# plen_headboard.net
KiCad netlist of a schematic drawn in EAGLE
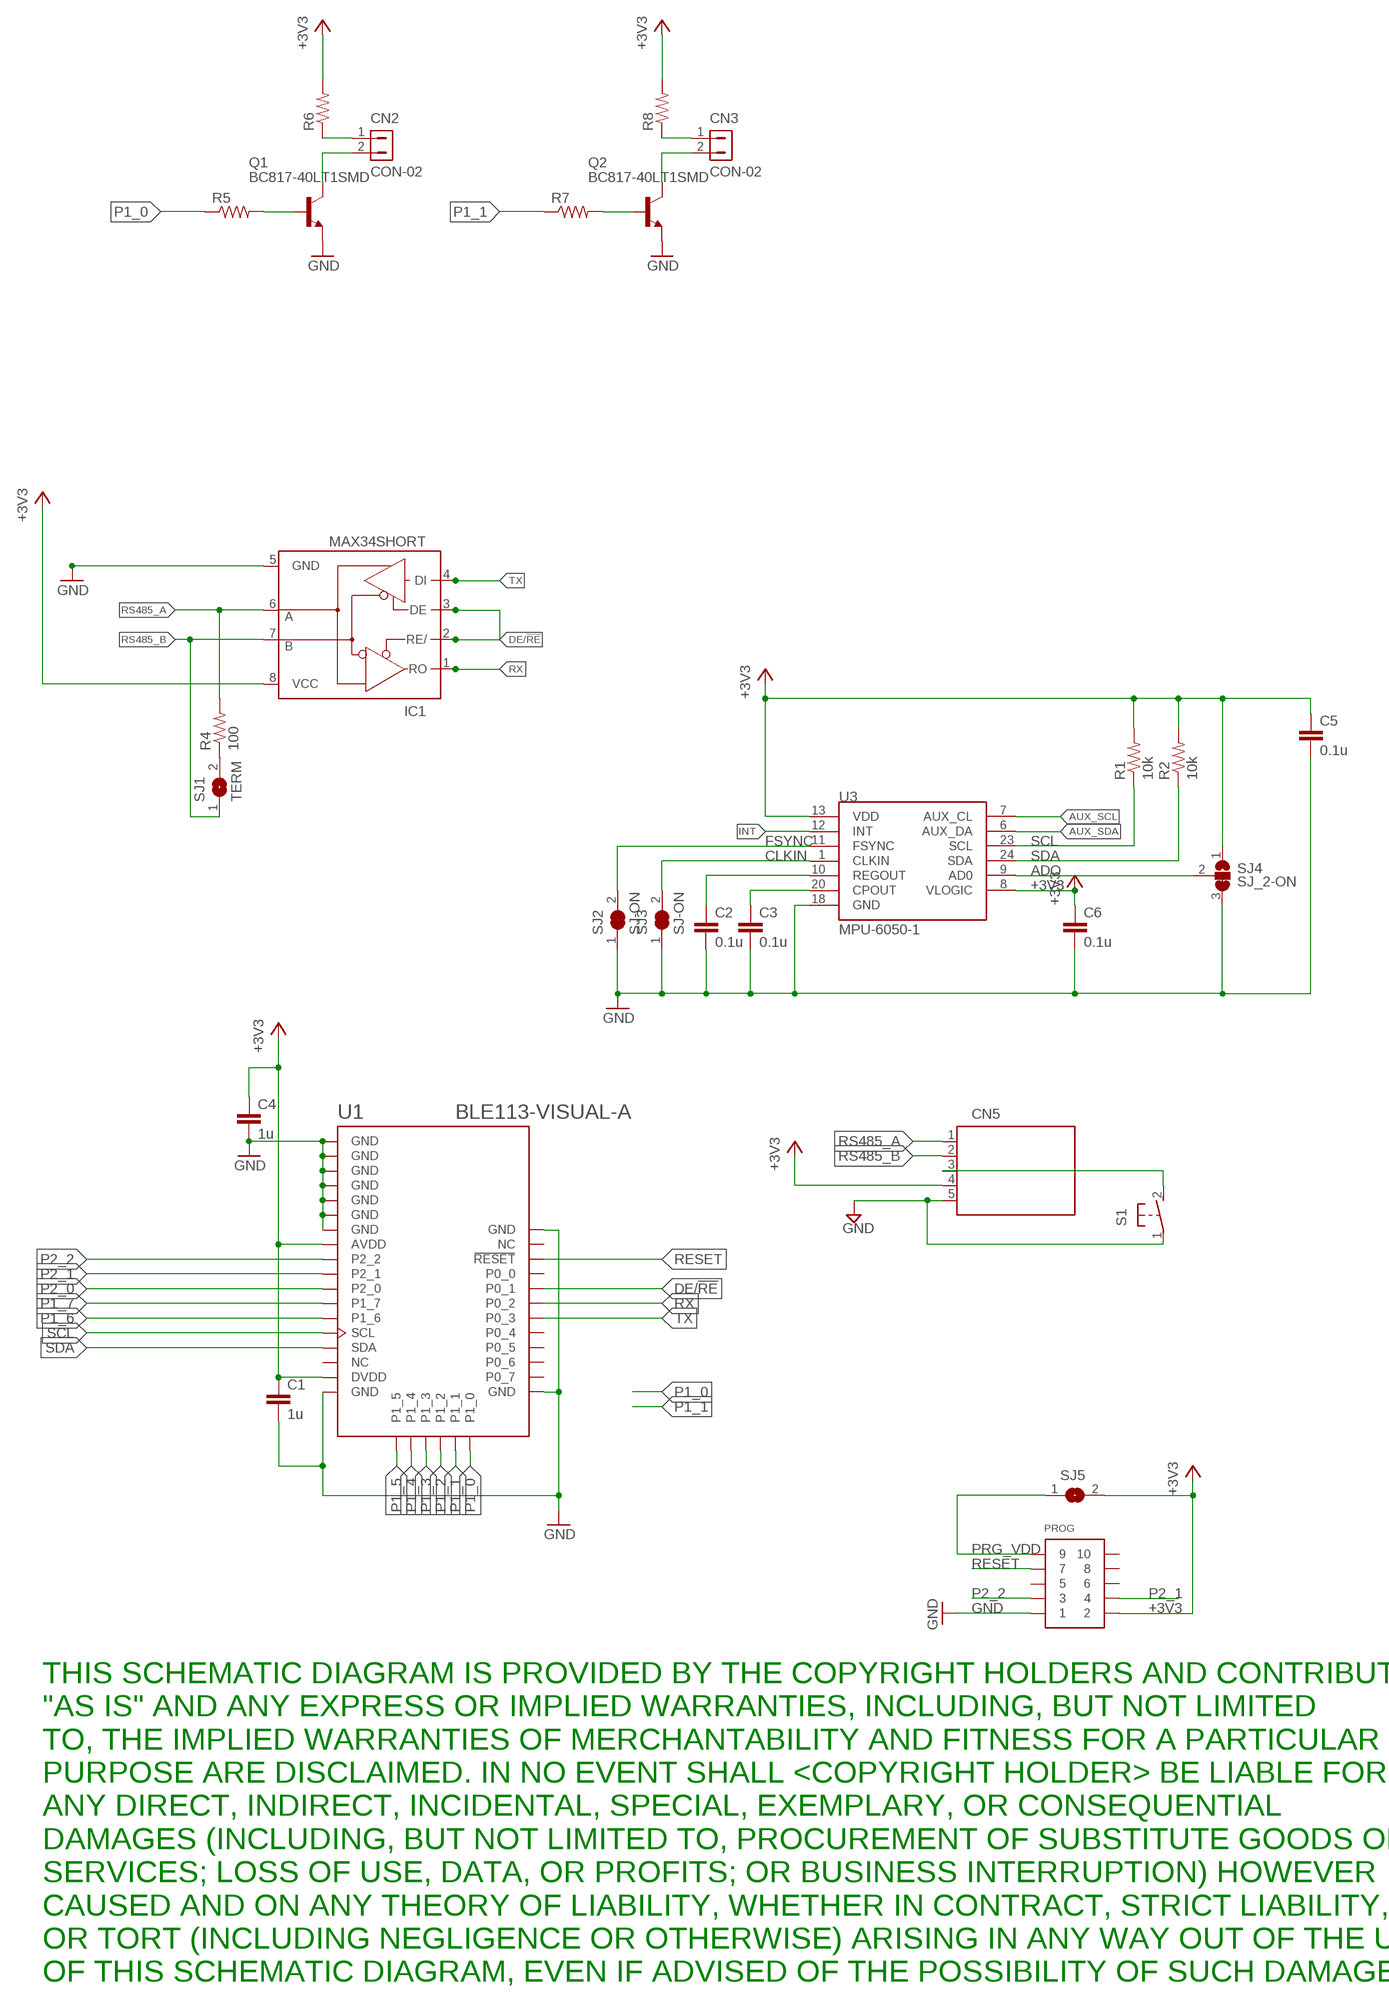
[diagram p0: schematic, sheet 1]

(export (version "E")
  (design (tool "Eeschema 10.0.6"))
  (components
    (comp (ref "C1")
      (value "1u")
      (footprint "eagle-import:C0603")
      (libsource (lib "eagle-import") (part "C-EUC0603"))
    )
    (comp (ref "C2")
      (value "0.1u")
      (footprint "eagle-import:C0603")
      (libsource (lib "eagle-import") (part "C-EUC0603"))
    )
    (comp (ref "C3")
      (value "0.1u")
      (footprint "eagle-import:C0603")
      (libsource (lib "eagle-import") (part "C-EUC0603"))
    )
    (comp (ref "C4")
      (value "1u")
      (footprint "eagle-import:C0603")
      (libsource (lib "eagle-import") (part "C-EUC0603"))
    )
    (comp (ref "C5")
      (value "0.1u")
      (footprint "eagle-import:C0603")
      (libsource (lib "eagle-import") (part "C-EUC0603"))
    )
    (comp (ref "C6")
      (value "0.1u")
      (footprint "eagle-import:C0603")
      (libsource (lib "eagle-import") (part "C-EUC0603"))
    )
    (comp (ref "CN2")
      (value "CON-02")
      (footprint "eagle-import:SIP-100-02")
      (libsource (lib "eagle-import") (part "CON-02"))
    )
    (comp (ref "CN3")
      (value "CON-02")
      (footprint "eagle-import:SIP-100-02")
      (libsource (lib "eagle-import") (part "CON-02"))
    )
    (comp (ref "CN5")
      (value "5PINZH")
      (footprint "eagle-import:ZH-5")
      (libsource (lib "eagle-import") (part "5PINZH"))
    )
    (comp (ref "IC1")
      (value "MAX34SHORT")
      (footprint "eagle-import:SO08SHORT")
      (libsource (lib "eagle-import") (part "MAX34SHORT"))
    )
    (comp (ref "PROG")
      (value "CONN_5-2-FTSH-V")
      (footprint "eagle-import:FTSH-105-DV")
      (libsource (lib "eagle-import") (part "CONN_5-2-FTSH-V"))
    )
    (comp (ref "Q1")
      (value "BC817-40LT1SMD")
      (footprint "eagle-import:SOT23-BEC")
      (libsource (lib "eagle-import") (part "BC817SMD-40LT1"))
    )
    (comp (ref "Q2")
      (value "BC817-40LT1SMD")
      (footprint "eagle-import:SOT23-BEC")
      (libsource (lib "eagle-import") (part "BC817SMD-40LT1"))
    )
    (comp (ref "R1")
      (value "10k")
      (footprint "eagle-import:R0603")
      (libsource (lib "eagle-import") (part "R-US_R0603"))
    )
    (comp (ref "R2")
      (value "10k")
      (footprint "eagle-import:R0603")
      (libsource (lib "eagle-import") (part "R-US_R0603"))
    )
    (comp (ref "R4")
      (value "100")
      (footprint "eagle-import:R0603")
      (libsource (lib "eagle-import") (part "R-US_R0603"))
    )
    (comp (ref "R5")
      (value "R-US_R0603")
      (footprint "eagle-import:R0603")
      (libsource (lib "eagle-import") (part "R-US_R0603"))
    )
    (comp (ref "R6")
      (value "R-US_R0603")
      (footprint "eagle-import:R0603")
      (libsource (lib "eagle-import") (part "R-US_R0603"))
    )
    (comp (ref "R7")
      (value "R-US_R0603")
      (footprint "eagle-import:R0603")
      (libsource (lib "eagle-import") (part "R-US_R0603"))
    )
    (comp (ref "R8")
      (value "R-US_R0603")
      (footprint "eagle-import:R0603")
      (libsource (lib "eagle-import") (part "R-US_R0603"))
    )
    (comp (ref "S1")
      (value "31-XX")
      (footprint "eagle-import:B3F-31XX")
      (fields (field (name "MPN") "B3F-3100"))
      (libsource (lib "eagle-import") (part "31-XX"))
    )
    (comp (ref "SJ1")
      (value "TERM")
      (footprint "eagle-import:SJ")
      (libsource (lib "eagle-import") (part "SJ"))
    )
    (comp (ref "SJ2")
      (value "SJ-ON")
      (footprint "eagle-import:SJ-ON")
      (libsource (lib "eagle-import") (part "SJ-ON"))
    )
    (comp (ref "SJ3")
      (value "SJ-ON")
      (footprint "eagle-import:SJ-ON")
      (libsource (lib "eagle-import") (part "SJ-ON"))
    )
    (comp (ref "SJ4")
      (value "SJ_2-ON")
      (footprint "eagle-import:SJ_2-ON")
      (libsource (lib "eagle-import") (part "SJ_2-ON"))
    )
    (comp (ref "SJ5") (value "SJ") (footprint "eagle-import:SJ") (libsource (lib "eagle-import") (part "SJ")))
    (comp (ref "U1")
      (value "BLE113-VISUAL-A")
      (footprint "eagle-import:BLE113-A")
      (libsource (lib "eagle-import") (part "BLE113-VISUAL-A"))
    )
    (comp (ref "U3")
      (value "MPU-6050-1")
      (footprint "eagle-import:QFN-24-4MM2")
      (libsource (lib "eagle-import") (part "MPU-6050-1"))
    )
  )
  (nets
    (net (code "1") (name "+3V3") (class "Default")
      (node (ref "C1") (pin "1") (pinfunction "1_1") (pintype "passive"))
      (node (ref "C4") (pin "1") (pinfunction "1_1") (pintype "passive"))
      (node (ref "C5") (pin "1") (pinfunction "1_1") (pintype "passive"))
      (node (ref "C6") (pin "1") (pinfunction "1_1") (pintype "passive"))
      (node (ref "CN5") (pin "4") (pinfunction "4_4") (pintype "passive"))
      (node (ref "IC1") (pin "8") (pinfunction "VCC_8") (pintype "power_in"))
      (node (ref "PROG") (pin "2") (pinfunction "2_2") (pintype "bidirectional"))
      (node (ref "R1") (pin "2") (pinfunction "2_2") (pintype "passive"))
      (node (ref "R2") (pin "2") (pinfunction "2_2") (pintype "passive"))
      (node (ref "R6") (pin "2") (pinfunction "2_2") (pintype "passive"))
      (node (ref "R8") (pin "2") (pinfunction "2_2") (pintype "passive"))
      (node (ref "SJ4") (pin "1") (pinfunction "1_1") (pintype "passive"))
      (node (ref "SJ5") (pin "2") (pinfunction "2_2") (pintype "passive"))
      (node (ref "U1") (pin "AVDD") (pinfunction "AVDD_AVDD") (pintype "power_in"))
      (node (ref "U1") (pin "DVDD") (pinfunction "DVDD_DVDD") (pintype "power_in"))
      (node (ref "U3") (pin "13") (pinfunction "VDD_13") (pintype "bidirectional"))
      (node (ref "U3") (pin "8") (pinfunction "VLOGIC_8") (pintype "bidirectional"))
    )
    (net (code "2") (name "/ADO") (class "Default")
      (node (ref "SJ4") (pin "2") (pinfunction "2_2") (pintype "passive"))
      (node (ref "U3") (pin "9") (pinfunction "AD0_9") (pintype "bidirectional"))
    )
    (net (code "3") (name "/CLKIN") (class "Default")
      (node (ref "SJ3") (pin "2") (pinfunction "2_2") (pintype "passive"))
      (node (ref "U3") (pin "1") (pinfunction "CLKIN_1") (pintype "bidirectional"))
    )
    (net (code "4") (name "/DE{slash}~{RE}") (class "Default")
      (node (ref "IC1") (pin "2") (pinfunction "RE/_2") (pintype "input"))
      (node (ref "IC1") (pin "3") (pinfunction "DE_3") (pintype "input"))
      (node (ref "U1") (pin "P0_1") (pinfunction "P0_1_P0_1") (pintype "bidirectional"))
    )
    (net (code "5") (name "/FSYNC") (class "Default")
      (node (ref "SJ2") (pin "2") (pinfunction "2_2") (pintype "passive"))
      (node (ref "U3") (pin "11") (pinfunction "FSYNC_11") (pintype "bidirectional"))
    )
    (net (code "6") (name "/PRG_VDD") (class "Default")
      (node (ref "PROG") (pin "9") (pinfunction "9_9") (pintype "bidirectional"))
      (node (ref "SJ5") (pin "1") (pinfunction "1_1") (pintype "passive"))
    )
    (net (code "7") (name "AUX_SCL") (class "Default")
      (node (ref "U3") (pin "7") (pinfunction "AUX_CL_7") (pintype "bidirectional"))
    )
    (net (code "8") (name "AUX_SDA") (class "Default")
      (node (ref "U3") (pin "6") (pinfunction "AUX_DA_6") (pintype "bidirectional"))
    )
    (net (code "9") (name "GND") (class "Default")
      (node (ref "C1") (pin "2") (pinfunction "2_2") (pintype "passive"))
      (node (ref "C2") (pin "2") (pinfunction "2_2") (pintype "passive"))
      (node (ref "C3") (pin "2") (pinfunction "2_2") (pintype "passive"))
      (node (ref "C4") (pin "2") (pinfunction "2_2") (pintype "passive"))
      (node (ref "C5") (pin "2") (pinfunction "2_2") (pintype "passive"))
      (node (ref "C6") (pin "2") (pinfunction "2_2") (pintype "passive"))
      (node (ref "CN5") (pin "5") (pinfunction "5_5") (pintype "passive"))
      (node (ref "IC1") (pin "5") (pinfunction "GND_5") (pintype "power_in"))
      (node (ref "PROG") (pin "1") (pinfunction "1_1") (pintype "bidirectional"))
      (node (ref "Q1") (pin "E") (pinfunction "E_E") (pintype "passive"))
      (node (ref "Q2") (pin "E") (pinfunction "E_E") (pintype "passive"))
      (node (ref "S1") (pin "1") (pinfunction "P_1") (pintype "passive"))
      (node (ref "SJ2") (pin "1") (pinfunction "1_1") (pintype "passive"))
      (node (ref "SJ3") (pin "1") (pinfunction "1_1") (pintype "passive"))
      (node (ref "SJ4") (pin "3") (pinfunction "3_3") (pintype "passive"))
      (node (ref "U1") (pin "GND") (pinfunction "GND_GND") (pintype "power_in"))
      (node (ref "U1") (pin "GND@10") (pinfunction "GND_GND@10") (pintype "power_in"))
      (node (ref "U1") (pin "GND@2") (pinfunction "GND_GND@2") (pintype "power_in"))
      (node (ref "U1") (pin "GND@3") (pinfunction "GND_GND@3") (pintype "power_in"))
      (node (ref "U1") (pin "GND@4") (pinfunction "GND_GND@4") (pintype "power_in"))
      (node (ref "U1") (pin "GND@5") (pinfunction "GND_GND@5") (pintype "power_in"))
      (node (ref "U1") (pin "GND@6") (pinfunction "GND_GND@6") (pintype "power_in"))
      (node (ref "U1") (pin "GND@7") (pinfunction "GND_GND@7") (pintype "power_in"))
      (node (ref "U1") (pin "GND@8") (pinfunction "GND_GND@8") (pintype "power_in"))
      (node (ref "U1") (pin "GND@9") (pinfunction "GND_GND@9") (pintype "power_in"))
      (node (ref "U3") (pin "18") (pinfunction "GND_18") (pintype "bidirectional"))
    )
    (net (code "10") (name "INT") (class "Default")
      (node (ref "U3") (pin "12") (pinfunction "INT_12") (pintype "bidirectional"))
    )
    (net (code "11") (name "Net-(CN2-Pad1)") (class "Default")
      (node (ref "CN2") (pin "1") (pinfunction "1_1") (pintype "passive"))
      (node (ref "R6") (pin "1") (pinfunction "1_1") (pintype "passive"))
    )
    (net (code "12") (name "Net-(CN2-Pad2)") (class "Default")
      (node (ref "CN2") (pin "2") (pinfunction "2_2") (pintype "passive"))
      (node (ref "Q1") (pin "C") (pinfunction "C_C") (pintype "passive"))
    )
    (net (code "13") (name "Net-(CN3-Pad1)") (class "Default")
      (node (ref "CN3") (pin "1") (pinfunction "1_1") (pintype "passive"))
      (node (ref "R8") (pin "1") (pinfunction "1_1") (pintype "passive"))
    )
    (net (code "14") (name "Net-(CN3-Pad2)") (class "Default")
      (node (ref "CN3") (pin "2") (pinfunction "2_2") (pintype "passive"))
      (node (ref "Q2") (pin "C") (pinfunction "C_C") (pintype "passive"))
    )
    (net (code "15") (name "Net-(Q1-PadB)") (class "Default")
      (node (ref "Q1") (pin "B") (pinfunction "B_B") (pintype "passive"))
      (node (ref "R5") (pin "2") (pinfunction "2_2") (pintype "passive"))
    )
    (net (code "16") (name "Net-(Q2-PadB)") (class "Default")
      (node (ref "Q2") (pin "B") (pinfunction "B_B") (pintype "passive"))
      (node (ref "R7") (pin "2") (pinfunction "2_2") (pintype "passive"))
    )
    (net (code "17") (name "Net-(R4-Pad1)") (class "Default")
      (node (ref "R4") (pin "1") (pinfunction "1_1") (pintype "passive"))
      (node (ref "SJ1") (pin "2") (pinfunction "2_2") (pintype "passive"))
    )
    (net (code "18") (name "Net-(S1-S)") (class "Default")
      (node (ref "CN5") (pin "3") (pinfunction "3_3") (pintype "passive"))
      (node (ref "S1") (pin "2") (pinfunction "S_2") (pintype "passive"))
    )
    (net (code "19") (name "Net-(U3-CPOUT)") (class "Default")
      (node (ref "C3") (pin "1") (pinfunction "1_1") (pintype "passive"))
      (node (ref "U3") (pin "20") (pinfunction "CPOUT_20") (pintype "bidirectional"))
    )
    (net (code "20") (name "Net-(U3-REGOUT)") (class "Default")
      (node (ref "C2") (pin "1") (pinfunction "1_1") (pintype "passive"))
      (node (ref "U3") (pin "10") (pinfunction "REGOUT_10") (pintype "bidirectional"))
    )
    (net (code "21") (name "P1_0") (class "Default")
      (node (ref "R5") (pin "1") (pinfunction "1_1") (pintype "passive"))
      (node (ref "U1") (pin "P1_0") (pinfunction "P1_0_P1_0") (pintype "bidirectional"))
    )
    (net (code "22") (name "P1_1") (class "Default")
      (node (ref "R7") (pin "1") (pinfunction "1_1") (pintype "passive"))
      (node (ref "U1") (pin "P1_1") (pinfunction "P1_1_P1_1") (pintype "bidirectional"))
    )
    (net (code "23") (name "P1_2") (class "Default")
      (node (ref "U1") (pin "P1_2") (pinfunction "P1_2_P1_2") (pintype "bidirectional"))
    )
    (net (code "24") (name "P1_3") (class "Default")
      (node (ref "U1") (pin "P1_3") (pinfunction "P1_3_P1_3") (pintype "bidirectional"))
    )
    (net (code "25") (name "P1_4") (class "Default")
      (node (ref "U1") (pin "P1_4") (pinfunction "P1_4_P1_4") (pintype "bidirectional"))
    )
    (net (code "26") (name "P1_5") (class "Default")
      (node (ref "U1") (pin "P1_5") (pinfunction "P1_5_P1_5") (pintype "bidirectional"))
    )
    (net (code "27") (name "P1_6") (class "Default")
      (node (ref "U1") (pin "P1_6") (pinfunction "P1_6_P1_6") (pintype "bidirectional"))
    )
    (net (code "28") (name "P1_7") (class "Default")
      (node (ref "U1") (pin "P1_7") (pinfunction "P1_7_P1_7") (pintype "bidirectional"))
    )
    (net (code "29") (name "P2_0") (class "Default")
      (node (ref "U1") (pin "P2_0") (pinfunction "P2_0_P2_0") (pintype "bidirectional"))
    )
    (net (code "30") (name "P2_1") (class "Default")
      (node (ref "PROG") (pin "4") (pinfunction "4_4") (pintype "bidirectional"))
      (node (ref "U1") (pin "P2_1") (pinfunction "P2_1_P2_1") (pintype "bidirectional"))
    )
    (net (code "31") (name "P2_2") (class "Default")
      (node (ref "PROG") (pin "3") (pinfunction "3_3") (pintype "bidirectional"))
      (node (ref "U1") (pin "P2_2") (pinfunction "P2_2_P2_2") (pintype "bidirectional"))
    )
    (net (code "32") (name "RESET") (class "Default")
      (node (ref "PROG") (pin "7") (pinfunction "7_7") (pintype "bidirectional"))
      (node (ref "U1") (pin "RESET") (pinfunction "RESET_RESET") (pintype "input"))
    )
    (net (code "33") (name "RS485_A") (class "Default")
      (node (ref "CN5") (pin "1") (pinfunction "1_1") (pintype "passive"))
      (node (ref "IC1") (pin "6") (pinfunction "A_6") (pintype "passive"))
      (node (ref "R4") (pin "2") (pinfunction "2_2") (pintype "passive"))
    )
    (net (code "34") (name "RS485_B") (class "Default")
      (node (ref "CN5") (pin "2") (pinfunction "2_2") (pintype "passive"))
      (node (ref "IC1") (pin "7") (pinfunction "B_7") (pintype "passive"))
      (node (ref "SJ1") (pin "1") (pinfunction "1_1") (pintype "passive"))
    )
    (net (code "35") (name "RX") (class "Default")
      (node (ref "IC1") (pin "1") (pinfunction "RO_1") (pintype "output"))
      (node (ref "U1") (pin "P0_2") (pinfunction "P0_2_P0_2") (pintype "bidirectional"))
    )
    (net (code "36") (name "SCL") (class "Default")
      (node (ref "R1") (pin "1") (pinfunction "1_1") (pintype "passive"))
      (node (ref "U1") (pin "SCL") (pinfunction "SCL_SCL") (pintype "bidirectional"))
      (node (ref "U3") (pin "23") (pinfunction "SCL_23") (pintype "bidirectional"))
    )
    (net (code "37") (name "SDA") (class "Default")
      (node (ref "R2") (pin "1") (pinfunction "1_1") (pintype "passive"))
      (node (ref "U1") (pin "SDA") (pinfunction "SDA_SDA") (pintype "bidirectional"))
      (node (ref "U3") (pin "24") (pinfunction "SDA_24") (pintype "bidirectional"))
    )
    (net (code "38") (name "TX") (class "Default")
      (node (ref "IC1") (pin "4") (pinfunction "DI_4") (pintype "input"))
      (node (ref "U1") (pin "P0_3") (pinfunction "P0_3_P0_3") (pintype "bidirectional"))
    )
    (net (code "39") (name "unconnected-(PROG-Pad5)") (class "Default")
      (node (ref "PROG") (pin "5") (pinfunction "5_5") (pintype "bidirectional"))
    )
    (net (code "40") (name "unconnected-(PROG-Pad6)") (class "Default")
      (node (ref "PROG") (pin "6") (pinfunction "6_6") (pintype "bidirectional"))
    )
    (net (code "41") (name "unconnected-(PROG-Pad8)") (class "Default")
      (node (ref "PROG") (pin "8") (pinfunction "8_8") (pintype "bidirectional"))
    )
    (net (code "42") (name "unconnected-(PROG-Pad10)") (class "Default")
      (node (ref "PROG") (pin "10") (pinfunction "10_10") (pintype "bidirectional"))
    )
    (net (code "43") (name "unconnected-(U1-NC-PadNC@2)") (class "Default")
      (node (ref "U1") (pin "NC@2") (pinfunction "NC_NC@2") (pintype "no_connect"))
    )
    (net (code "44") (name "unconnected-(U1-PadNC)") (class "Default")
      (node (ref "U1") (pin "NC") (pinfunction "NC_NC") (pintype "no_connect"))
    )
    (net (code "45") (name "unconnected-(U1-PadP0_0)") (class "Default")
      (node (ref "U1") (pin "P0_0") (pinfunction "P0_0_P0_0") (pintype "bidirectional"))
    )
    (net (code "46") (name "unconnected-(U1-PadP0_4)") (class "Default")
      (node (ref "U1") (pin "P0_4") (pinfunction "P0_4_P0_4") (pintype "bidirectional"))
    )
    (net (code "47") (name "unconnected-(U1-PadP0_5)") (class "Default")
      (node (ref "U1") (pin "P0_5") (pinfunction "P0_5_P0_5") (pintype "bidirectional"))
    )
    (net (code "48") (name "unconnected-(U1-PadP0_6)") (class "Default")
      (node (ref "U1") (pin "P0_6") (pinfunction "P0_6_P0_6") (pintype "bidirectional"))
    )
    (net (code "49") (name "unconnected-(U1-PadP0_7)") (class "Default")
      (node (ref "U1") (pin "P0_7") (pinfunction "P0_7_P0_7") (pintype "bidirectional"))
    )
  )
)
